# 2CH_Digital_Isolator.net
KiCad netlist of a schematic drawn in Altium Designer
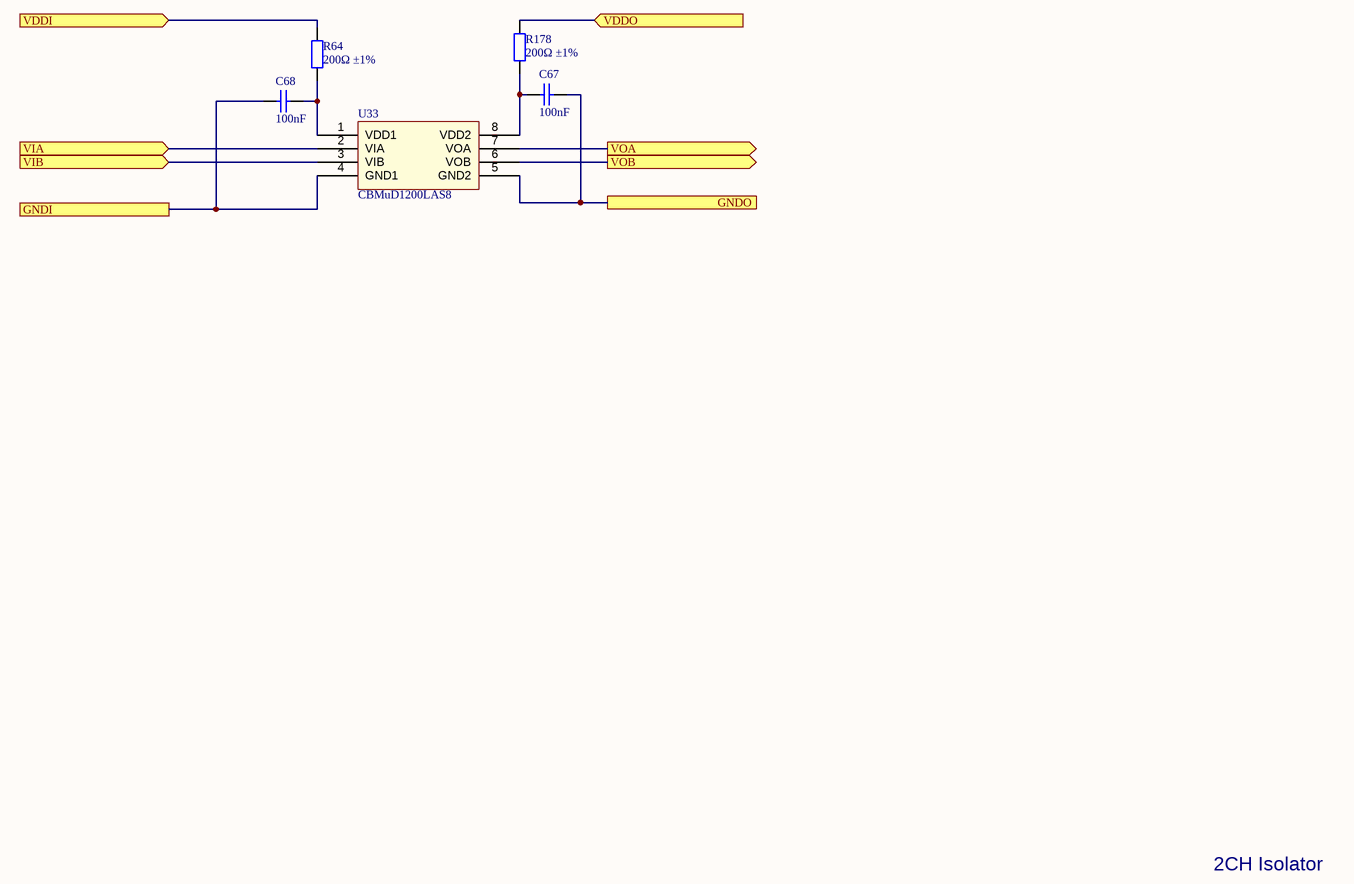
[diagram p0: 2CH_Digital_Isolator.SchDoc]

(export (version "E")
  (design (tool "Eeschema 10.0.6"))
  (components
    (comp (ref "C67")
      (value "100nF")
      (footprint "0603_C")
      (description "Chip capacitors")
      (fields (field (name "MANUFACTURER") "YAGEO") (field (name "PARTNUMBER") "CC0603KRX7R9BB104"))
      (libsource (lib "Cap") (part "0603 100nF (104) 10% 50V"))
    )
    (comp (ref "C68")
      (value "100nF")
      (footprint "0603_C")
      (description "Chip capacitors")
      (fields (field (name "MANUFACTURER") "YAGEO") (field (name "PARTNUMBER") "CC0603KRX7R9BB104"))
      (libsource (lib "Cap") (part "0603 100nF (104) 10% 50V"))
    )
    (comp (ref "R64")
      (value "200Ω ±1%")
      (footprint "0603_R")
      (description "Chip resistor")
      (fields (field (name "MANUFACTURER") "Uniroyal Elec") (field (name "PARTNUMBER") "0603WAF2000T5E"))
      (libsource (lib "RES") (part "0603 200R (2000) 1%"))
    )
    (comp (ref "R178")
      (value "200Ω ±1%")
      (footprint "0603_R")
      (description "Chip resistor")
      (fields (field (name "MANUFACTURER") "Uniroyal Elec") (field (name "PARTNUMBER") "0603WAF2000T5E"))
      (libsource (lib "RES") (part "0603 200R (2000) 1%"))
    )
    (comp (ref "U33")
      (value "CBMuD1200LAS8")
      (footprint "SOIC-8_150mil")
      (description "Dual Channel Isolator")
      (libsource (lib "IC") (part "CBMuD1200LAS8"))
    )
  )
  (nets
    (net (code "1") (name "/GNDI") (class "Default")
      (node (ref "C68") (pin "2") (pinfunction "2_2") (pintype "passive"))
      (node (ref "U33") (pin "4") (pinfunction "GND1_4") (pintype "passive"))
    )
    (net (code "2") (name "/GNDO") (class "Default")
      (node (ref "C67") (pin "1") (pinfunction "1_1") (pintype "passive"))
      (node (ref "U33") (pin "5") (pinfunction "GND2_5") (pintype "passive"))
    )
    (net (code "3") (name "/VDDI") (class "Default")
      (node (ref "R64") (pin "2") (pinfunction "2_2") (pintype "passive"))
    )
    (net (code "4") (name "/VDDO") (class "Default")
      (node (ref "R178") (pin "2") (pinfunction "2_2") (pintype "passive"))
    )
    (net (code "5") (name "/VIA") (class "Default")
      (node (ref "U33") (pin "2") (pinfunction "VIA_2") (pintype "passive"))
    )
    (net (code "6") (name "/VIB") (class "Default")
      (node (ref "U33") (pin "3") (pinfunction "VIB_3") (pintype "passive"))
    )
    (net (code "7") (name "/VOA") (class "Default")
      (node (ref "U33") (pin "7") (pinfunction "VOA_7") (pintype "passive"))
    )
    (net (code "8") (name "/VOB") (class "Default")
      (node (ref "U33") (pin "6") (pinfunction "VOB_6") (pintype "passive"))
    )
    (net (code "9") (name "Net-(U33-VDD1)") (class "Default")
      (node (ref "C68") (pin "1") (pinfunction "1_1") (pintype "passive"))
      (node (ref "R64") (pin "1") (pinfunction "1_1") (pintype "passive"))
      (node (ref "U33") (pin "1") (pinfunction "VDD1_1") (pintype "passive"))
    )
    (net (code "10") (name "Net-(U33-VDD2)") (class "Default")
      (node (ref "C67") (pin "2") (pinfunction "2_2") (pintype "passive"))
      (node (ref "R178") (pin "1") (pinfunction "1_1") (pintype "passive"))
      (node (ref "U33") (pin "8") (pinfunction "VDD2_8") (pintype "passive"))
    )
  )
)
